# OMNIBUS_Stepper_board_v2.net
KiCad netlist of a schematic drawn in EAGLE
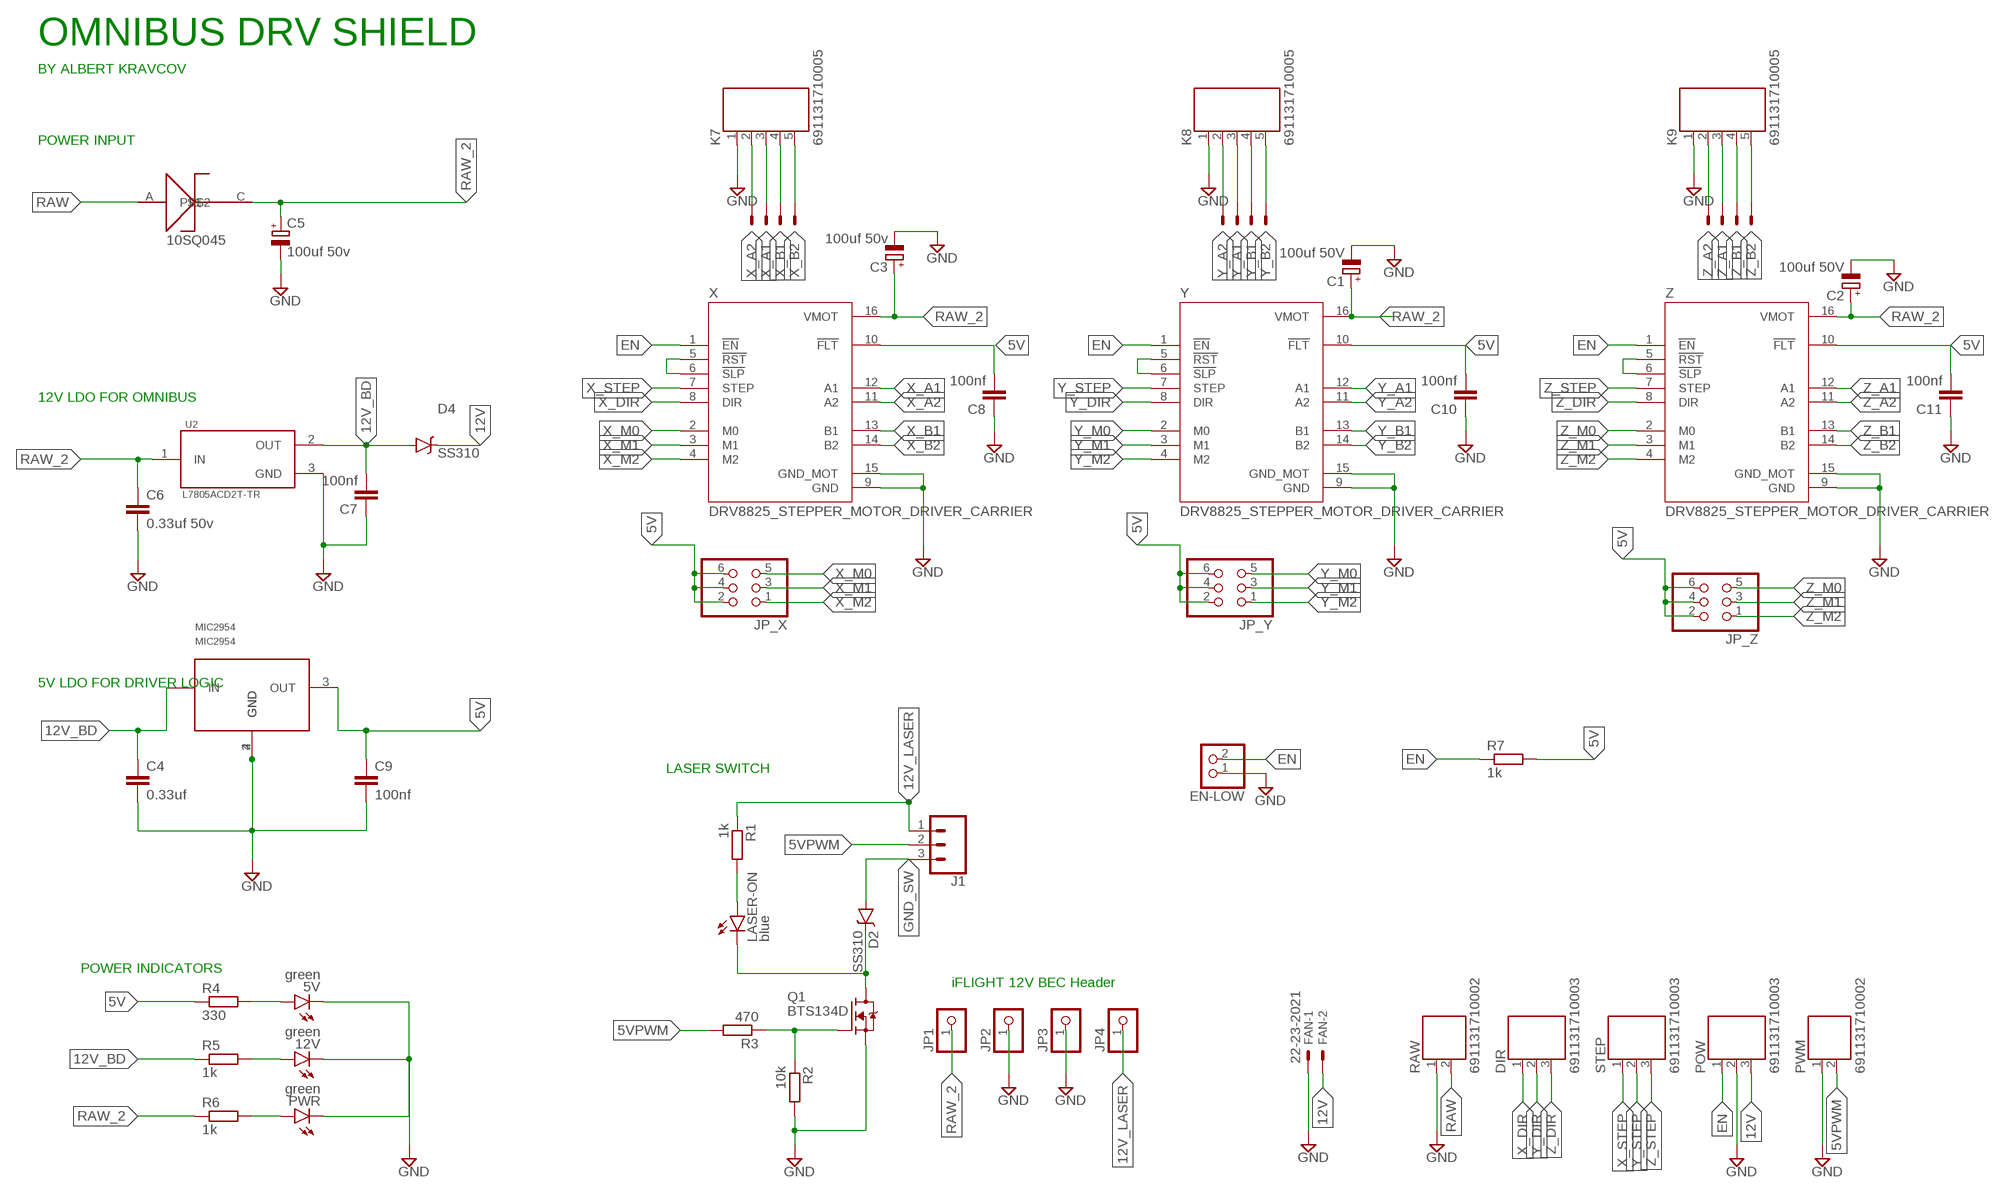
[diagram p0: schematic, sheet 1]

(export (version "E")
  (design (tool "Eeschema 10.0.6"))
  (components
    (comp (ref "5V")
      (value "green")
      (footprint "eagle-import:CHIPLED_0805")
      (libsource (lib "eagle-import") (part "LEDCHIPLED_0805"))
    )
    (comp (ref "12V")
      (value "green")
      (footprint "eagle-import:CHIPLED_0805")
      (libsource (lib "eagle-import") (part "LEDCHIPLED_0805"))
    )
    (comp (ref "C1")
      (value "100uf 50V")
      (footprint "eagle-import:E5-6")
      (libsource (lib "eagle-import") (part "CPOL-EUE5-6"))
    )
    (comp (ref "C2")
      (value "100uf 50V")
      (footprint "eagle-import:E5-6")
      (libsource (lib "eagle-import") (part "CPOL-EUE5-6"))
    )
    (comp (ref "C3")
      (value "100uf 50v")
      (footprint "eagle-import:E5-6")
      (libsource (lib "eagle-import") (part "CPOL-EUE5-6"))
    )
    (comp (ref "C4")
      (value "0.33uf")
      (footprint "eagle-import:C1206")
      (libsource (lib "eagle-import") (part "C-EUC1206"))
    )
    (comp (ref "C5")
      (value "100uf 50v")
      (footprint "eagle-import:E5-8,5")
      (libsource (lib "eagle-import") (part "rcl_334_CPOL-EUE5-8.5"))
    )
    (comp (ref "C6")
      (value "0.33uf 50v")
      (footprint "eagle-import:C1206")
      (libsource (lib "eagle-import") (part "C-EUC1206"))
    )
    (comp (ref "C7")
      (value "100nf")
      (footprint "eagle-import:C0805")
      (libsource (lib "eagle-import") (part "C-EUC0805"))
    )
    (comp (ref "C8")
      (value "100nf")
      (footprint "eagle-import:C0805")
      (libsource (lib "eagle-import") (part "C-EUC0805"))
    )
    (comp (ref "C9")
      (value "100nf")
      (footprint "eagle-import:C1206")
      (libsource (lib "eagle-import") (part "C-EUC1206"))
    )
    (comp (ref "C10")
      (value "100nf")
      (footprint "eagle-import:C0805")
      (libsource (lib "eagle-import") (part "C-EUC0805"))
    )
    (comp (ref "C11")
      (value "100nf")
      (footprint "eagle-import:C0805")
      (libsource (lib "eagle-import") (part "C-EUC0805"))
    )
    (comp (ref "D1")
      (value "10SQ045")
      (footprint "eagle-import:DIOAD885W125L910D885")
      (libsource (lib "eagle-import") (part "10SQ050"))
    )
    (comp (ref "D2")
      (value "SS310")
      (footprint "eagle-import:DO-214AC")
      (fields (field (name "MF") "Honeywell Sensing") (field (name "MP") "SS54"))
      (libsource (lib "eagle-import") (part "SS54"))
    )
    (comp (ref "D4")
      (value "SS310")
      (footprint "eagle-import:DO-214AC")
      (fields (field (name "MF") "Honeywell Sensing") (field (name "MP") "SS54"))
      (libsource (lib "eagle-import") (part "SS54"))
    )
    (comp (ref "DIR")
      (value "691131710003")
      (footprint "eagle-import:691131710003")
      (libsource (lib "eagle-import") (part "691131710003"))
    )
    (comp (ref "EN-LOW")
      (value "PINHD-1X2")
      (footprint "eagle-import:1X02")
      (libsource (lib "eagle-import") (part "PINHD-1X2"))
    )
    (comp (ref "FAN")
      (value "22-23-2021")
      (footprint "eagle-import:22-23-2021")
      (fields (field (name "MF") "MOLEX"))
      (libsource (lib "eagle-import") (part "22-23-2021"))
    )
    (comp (ref "J1")
      (value "CONN_03")
      (footprint "eagle-import:1X03")
      (libsource (lib "eagle-import") (part "CONN_03"))
    )
    (comp (ref "JP1")
      (value "PINHD-1X1")
      (footprint "eagle-import:1X01")
      (libsource (lib "eagle-import") (part "PINHD-1X1"))
    )
    (comp (ref "JP2")
      (value "PINHD-1X1")
      (footprint "eagle-import:1X01")
      (libsource (lib "eagle-import") (part "PINHD-1X1"))
    )
    (comp (ref "JP3")
      (value "PINHD-1X1")
      (footprint "eagle-import:1X01")
      (libsource (lib "eagle-import") (part "PINHD-1X1"))
    )
    (comp (ref "JP4")
      (value "PINHD-1X1")
      (footprint "eagle-import:1X01")
      (libsource (lib "eagle-import") (part "PINHD-1X1"))
    )
    (comp (ref "JP_X")
      (value "PINHD-2X3")
      (footprint "eagle-import:2X03")
      (libsource (lib "eagle-import") (part "PINHD-2X3"))
    )
    (comp (ref "JP_Y")
      (value "PINHD-2X3")
      (footprint "eagle-import:2X03")
      (libsource (lib "eagle-import") (part "PINHD-2X3"))
    )
    (comp (ref "JP_Z")
      (value "PINHD-2X3")
      (footprint "eagle-import:2X03")
      (libsource (lib "eagle-import") (part "PINHD-2X3"))
    )
    (comp (ref "K7")
      (value "691131710005")
      (footprint "eagle-import:691131710005")
      (libsource (lib "eagle-import") (part "691131710005"))
    )
    (comp (ref "K8")
      (value "691131710005")
      (footprint "eagle-import:691131710005")
      (libsource (lib "eagle-import") (part "691131710005"))
    )
    (comp (ref "K9")
      (value "691131710005")
      (footprint "eagle-import:691131710005")
      (libsource (lib "eagle-import") (part "691131710005"))
    )
    (comp (ref "LASER-ON")
      (value "blue")
      (footprint "eagle-import:CHIPLED_0805")
      (libsource (lib "eagle-import") (part "LEDCHIPLED_0805"))
    )
    (comp (ref "MIC2954")
      (value "MIC2954")
      (footprint "eagle-import:SOT223")
      (fields (field (name "MF") "Micrel"))
      (libsource (lib "eagle-import") (part "MIC2954"))
    )
    (comp (ref "POW")
      (value "691131710003")
      (footprint "eagle-import:691131710003")
      (libsource (lib "eagle-import") (part "691131710003"))
    )
    (comp (ref "PWM")
      (value "691131710002")
      (footprint "eagle-import:691131710002")
      (libsource (lib "eagle-import") (part "691131710002"))
    )
    (comp (ref "PWR")
      (value "green")
      (footprint "eagle-import:CHIPLED_0805")
      (libsource (lib "eagle-import") (part "LEDCHIPLED_0805"))
    )
    (comp (ref "Q1")
      (value "BTS134D")
      (footprint "eagle-import:TO-252")
      (fields (field (name "MF") "ON Semiconductor") (field (name "MP") "FQD7N10LTM"))
      (libsource (lib "eagle-import") (part "FQD7N10LTM"))
    )
    (comp (ref "R1")
      (value "1k")
      (footprint "eagle-import:R0805")
      (libsource (lib "eagle-import") (part "R-EU_R0805"))
    )
    (comp (ref "R2")
      (value "10k")
      (footprint "eagle-import:R0805")
      (libsource (lib "eagle-import") (part "R-EU_R0805"))
    )
    (comp (ref "R3")
      (value "470")
      (footprint "eagle-import:R0805")
      (libsource (lib "eagle-import") (part "R-EU_R0805"))
    )
    (comp (ref "R4")
      (value "330")
      (footprint "eagle-import:R0805")
      (libsource (lib "eagle-import") (part "R-EU_R0805"))
    )
    (comp (ref "R5")
      (value "1k")
      (footprint "eagle-import:R0805")
      (libsource (lib "eagle-import") (part "R-EU_R0805"))
    )
    (comp (ref "R6")
      (value "1k")
      (footprint "eagle-import:R1206")
      (libsource (lib "eagle-import") (part "R-EU_R1206"))
    )
    (comp (ref "R7")
      (value "1k")
      (footprint "eagle-import:R0805")
      (libsource (lib "eagle-import") (part "R-EU_R0805"))
    )
    (comp (ref "RAW")
      (value "691131710002")
      (footprint "eagle-import:691131710002")
      (libsource (lib "eagle-import") (part "691131710002"))
    )
    (comp (ref "STEP")
      (value "691131710003")
      (footprint "eagle-import:691131710003")
      (libsource (lib "eagle-import") (part "691131710003"))
    )
    (comp (ref "U2")
      (value "L7805ACD2T-TR")
      (footprint "eagle-import:TO254P1515X470-3N")
      (fields (field (name "MF") "STMicroelectronics"))
      (libsource (lib "eagle-import") (part "L7805ACD2T-TR"))
    )
    (comp (ref "X")
      (value "DRV8825_STEPPER_MOTOR_DRIVER_CARRIER")
      (footprint "eagle-import:IC_DRV8825_STEPPER_MOTOR_DRIVER_CARRIER")
      (fields (field (name "MF") "Pololu") (field (name "MP") "DRV8825 STEPPER MOTOR DRIVER CARRIER"))
      (libsource (lib "eagle-import") (part "DRV8825_STEPPER_MOTOR_DRIVER_CARRIER"))
    )
    (comp (ref "X_MOTOR")
      (value "22-23-2041")
      (footprint "eagle-import:22-23-2041")
      (fields (field (name "MF") "MOLEX"))
      (libsource (lib "eagle-import") (part "22-23-2041"))
    )
    (comp (ref "Y")
      (value "DRV8825_STEPPER_MOTOR_DRIVER_CARRIER")
      (footprint "eagle-import:IC_DRV8825_STEPPER_MOTOR_DRIVER_CARRIER")
      (fields (field (name "MF") "Pololu") (field (name "MP") "DRV8825 STEPPER MOTOR DRIVER CARRIER"))
      (libsource (lib "eagle-import") (part "DRV8825_STEPPER_MOTOR_DRIVER_CARRIER"))
    )
    (comp (ref "Y_MOTOR")
      (value "22-23-2041")
      (footprint "eagle-import:22-23-2041")
      (fields (field (name "MF") "MOLEX"))
      (libsource (lib "eagle-import") (part "22-23-2041"))
    )
    (comp (ref "Z")
      (value "DRV8825_STEPPER_MOTOR_DRIVER_CARRIER")
      (footprint "eagle-import:IC_DRV8825_STEPPER_MOTOR_DRIVER_CARRIER")
      (fields (field (name "MF") "Pololu") (field (name "MP") "DRV8825 STEPPER MOTOR DRIVER CARRIER"))
      (libsource (lib "eagle-import") (part "DRV8825_STEPPER_MOTOR_DRIVER_CARRIER"))
    )
    (comp (ref "Z_MOTOR")
      (value "22-23-2041")
      (footprint "eagle-import:22-23-2041")
      (fields (field (name "MF") "MOLEX"))
      (libsource (lib "eagle-import") (part "22-23-2041"))
    )
  )
  (nets
    (net (code "1") (name "5V") (class "Default")
      (node (ref "C10") (pin "2") (pinfunction "2_2") (pintype "passive"))
      (node (ref "C11") (pin "2") (pinfunction "2_2") (pintype "passive"))
      (node (ref "C8") (pin "2") (pinfunction "2_2") (pintype "passive"))
      (node (ref "C9") (pin "1") (pinfunction "1_1") (pintype "passive"))
      (node (ref "JP_X") (pin "2") (pinfunction "2_2") (pintype "passive"))
      (node (ref "JP_X") (pin "4") (pinfunction "4_4") (pintype "passive"))
      (node (ref "JP_X") (pin "6") (pinfunction "6_6") (pintype "passive"))
      (node (ref "JP_Y") (pin "2") (pinfunction "2_2") (pintype "passive"))
      (node (ref "JP_Y") (pin "4") (pinfunction "4_4") (pintype "passive"))
      (node (ref "JP_Y") (pin "6") (pinfunction "6_6") (pintype "passive"))
      (node (ref "JP_Z") (pin "2") (pinfunction "2_2") (pintype "passive"))
      (node (ref "JP_Z") (pin "4") (pinfunction "4_4") (pintype "passive"))
      (node (ref "JP_Z") (pin "6") (pinfunction "6_6") (pintype "passive"))
      (node (ref "MIC2954") (pin "3") (pinfunction "OUT_3") (pintype "bidirectional"))
      (node (ref "R4") (pin "1") (pinfunction "1_1") (pintype "passive"))
      (node (ref "R7") (pin "2") (pinfunction "2_2") (pintype "passive"))
      (node (ref "X") (pin "10") (pinfunction "~{FLT}_10") (pintype "output"))
      (node (ref "Y") (pin "10") (pinfunction "~{FLT}_10") (pintype "output"))
      (node (ref "Z") (pin "10") (pinfunction "~{FLT}_10") (pintype "output"))
    )
    (net (code "2") (name "5VPWM") (class "Default")
      (node (ref "J1") (pin "2") (pinfunction "2_2") (pintype "passive"))
      (node (ref "PWM") (pin "2") (pinfunction "2_2") (pintype "passive"))
      (node (ref "R3") (pin "2") (pinfunction "2_2") (pintype "passive"))
    )
    (net (code "3") (name "12V") (class "Default")
      (node (ref "D4") (pin "C") (pinfunction "C_C") (pintype "passive"))
      (node (ref "FAN") (pin "2") (pinfunction "S_2") (pintype "passive"))
      (node (ref "POW") (pin "3") (pinfunction "3_3") (pintype "passive"))
    )
    (net (code "4") (name "12V_BD") (class "Default")
      (node (ref "C4") (pin "1") (pinfunction "1_1") (pintype "passive"))
      (node (ref "C7") (pin "2") (pinfunction "2_2") (pintype "passive"))
      (node (ref "D4") (pin "A") (pinfunction "A_A") (pintype "passive"))
      (node (ref "MIC2954") (pin "1") (pinfunction "IN_1") (pintype "bidirectional"))
      (node (ref "R5") (pin "1") (pinfunction "1_1") (pintype "passive"))
      (node (ref "U2") (pin "2") (pinfunction "OUT_2") (pintype "output"))
    )
    (net (code "5") (name "12V_LASER") (class "Default")
      (node (ref "J1") (pin "1") (pinfunction "1_1") (pintype "passive"))
      (node (ref "JP4") (pin "1") (pinfunction "1_1") (pintype "passive"))
      (node (ref "R1") (pin "1") (pinfunction "1_1") (pintype "passive"))
    )
    (net (code "6") (name "EN") (class "Default")
      (node (ref "EN-LOW") (pin "2") (pinfunction "2_2") (pintype "passive"))
      (node (ref "POW") (pin "1") (pinfunction "1_1") (pintype "passive"))
      (node (ref "R7") (pin "1") (pinfunction "1_1") (pintype "passive"))
      (node (ref "X") (pin "1") (pinfunction "~{EN}_1") (pintype "input"))
      (node (ref "Y") (pin "1") (pinfunction "~{EN}_1") (pintype "input"))
      (node (ref "Z") (pin "1") (pinfunction "~{EN}_1") (pintype "input"))
    )
    (net (code "7") (name "GND") (class "Default")
      (node (ref "12V") (pin "C") (pinfunction "C_C") (pintype "passive"))
      (node (ref "5V") (pin "C") (pinfunction "C_C") (pintype "passive"))
      (node (ref "C1") (pin "-") (pinfunction "-_-") (pintype "passive"))
      (node (ref "C10") (pin "1") (pinfunction "1_1") (pintype "passive"))
      (node (ref "C11") (pin "1") (pinfunction "1_1") (pintype "passive"))
      (node (ref "C2") (pin "-") (pinfunction "-_-") (pintype "passive"))
      (node (ref "C3") (pin "-") (pinfunction "-_-") (pintype "passive"))
      (node (ref "C4") (pin "2") (pinfunction "2_2") (pintype "passive"))
      (node (ref "C5") (pin "-") (pinfunction "-_-") (pintype "passive"))
      (node (ref "C6") (pin "2") (pinfunction "2_2") (pintype "passive"))
      (node (ref "C7") (pin "1") (pinfunction "1_1") (pintype "passive"))
      (node (ref "C8") (pin "1") (pinfunction "1_1") (pintype "passive"))
      (node (ref "C9") (pin "2") (pinfunction "2_2") (pintype "passive"))
      (node (ref "EN-LOW") (pin "1") (pinfunction "1_1") (pintype "passive"))
      (node (ref "FAN") (pin "1") (pinfunction "S_1") (pintype "passive"))
      (node (ref "JP2") (pin "1") (pinfunction "1_1") (pintype "passive"))
      (node (ref "JP3") (pin "1") (pinfunction "1_1") (pintype "passive"))
      (node (ref "K7") (pin "1") (pinfunction "1_1") (pintype "passive"))
      (node (ref "K8") (pin "1") (pinfunction "1_1") (pintype "passive"))
      (node (ref "K9") (pin "1") (pinfunction "1_1") (pintype "passive"))
      (node (ref "MIC2954") (pin "2") (pinfunction "GND_2") (pintype "bidirectional"))
      (node (ref "MIC2954") (pin "4") (pinfunction "GND_4") (pintype "bidirectional"))
      (node (ref "POW") (pin "2") (pinfunction "2_2") (pintype "passive"))
      (node (ref "PWM") (pin "1") (pinfunction "1_1") (pintype "passive"))
      (node (ref "PWR") (pin "C") (pinfunction "C_C") (pintype "passive"))
      (node (ref "Q1") (pin "3") (pinfunction "S_3") (pintype "passive"))
      (node (ref "R2") (pin "2") (pinfunction "2_2") (pintype "passive"))
      (node (ref "RAW") (pin "1") (pinfunction "1_1") (pintype "passive"))
      (node (ref "U2") (pin "3") (pinfunction "GND_3") (pintype "power_in"))
      (node (ref "X") (pin "15") (pinfunction "GND_MOT_15") (pintype "power_in"))
      (node (ref "X") (pin "9") (pinfunction "GND_9") (pintype "power_in"))
      (node (ref "Y") (pin "15") (pinfunction "GND_MOT_15") (pintype "power_in"))
      (node (ref "Y") (pin "9") (pinfunction "GND_9") (pintype "power_in"))
      (node (ref "Z") (pin "15") (pinfunction "GND_MOT_15") (pintype "power_in"))
      (node (ref "Z") (pin "9") (pinfunction "GND_9") (pintype "power_in"))
    )
    (net (code "8") (name "GND_SW") (class "Default")
      (node (ref "D2") (pin "A") (pinfunction "A_A") (pintype "passive"))
      (node (ref "J1") (pin "3") (pinfunction "3_3") (pintype "passive"))
    )
    (net (code "9") (name "Net-(5V-PadA)") (class "Default")
      (node (ref "5V") (pin "A") (pinfunction "A_A") (pintype "passive"))
      (node (ref "R4") (pin "2") (pinfunction "2_2") (pintype "passive"))
    )
    (net (code "10") (name "Net-(12V-PadA)") (class "Default")
      (node (ref "12V") (pin "A") (pinfunction "A_A") (pintype "passive"))
      (node (ref "R5") (pin "2") (pinfunction "2_2") (pintype "passive"))
    )
    (net (code "11") (name "Net-(LASER-ON-PadA)") (class "Default")
      (node (ref "LASER-ON") (pin "A") (pinfunction "A_A") (pintype "passive"))
      (node (ref "R1") (pin "2") (pinfunction "2_2") (pintype "passive"))
    )
    (net (code "12") (name "Net-(PWR-PadA)") (class "Default")
      (node (ref "PWR") (pin "A") (pinfunction "A_A") (pintype "passive"))
      (node (ref "R6") (pin "2") (pinfunction "2_2") (pintype "passive"))
    )
    (net (code "13") (name "Net-(Q1-D)") (class "Default")
      (node (ref "D2") (pin "C") (pinfunction "C_C") (pintype "passive"))
      (node (ref "LASER-ON") (pin "C") (pinfunction "C_C") (pintype "passive"))
      (node (ref "Q1") (pin "T") (pinfunction "D_T") (pintype "passive"))
    )
    (net (code "14") (name "Net-(Q1-G)") (class "Default")
      (node (ref "Q1") (pin "1") (pinfunction "G_1") (pintype "passive"))
      (node (ref "R2") (pin "1") (pinfunction "1_1") (pintype "passive"))
      (node (ref "R3") (pin "1") (pinfunction "1_1") (pintype "passive"))
    )
    (net (code "15") (name "Net-(X-~{RST})") (class "Default")
      (node (ref "X") (pin "5") (pinfunction "~{RST}_5") (pintype "input"))
      (node (ref "X") (pin "6") (pinfunction "~{SLP}_6") (pintype "input"))
    )
    (net (code "16") (name "Net-(Y-~{RST})") (class "Default")
      (node (ref "Y") (pin "5") (pinfunction "~{RST}_5") (pintype "input"))
      (node (ref "Y") (pin "6") (pinfunction "~{SLP}_6") (pintype "input"))
    )
    (net (code "17") (name "Net-(Z-~{RST})") (class "Default")
      (node (ref "Z") (pin "5") (pinfunction "~{RST}_5") (pintype "input"))
      (node (ref "Z") (pin "6") (pinfunction "~{SLP}_6") (pintype "input"))
    )
    (net (code "18") (name "RAW") (class "Default")
      (node (ref "D1") (pin "A") (pinfunction "P$1_A") (pintype "bidirectional"))
      (node (ref "RAW") (pin "2") (pinfunction "2_2") (pintype "passive"))
    )
    (net (code "19") (name "RAW_2") (class "Default")
      (node (ref "C1") (pin "+") (pinfunction "+_+") (pintype "passive"))
      (node (ref "C2") (pin "+") (pinfunction "+_+") (pintype "passive"))
      (node (ref "C3") (pin "+") (pinfunction "+_+") (pintype "passive"))
      (node (ref "C5") (pin "+") (pinfunction "+_+") (pintype "passive"))
      (node (ref "C6") (pin "1") (pinfunction "1_1") (pintype "passive"))
      (node (ref "D1") (pin "C") (pinfunction "P$2_C") (pintype "bidirectional"))
      (node (ref "JP1") (pin "1") (pinfunction "1_1") (pintype "passive"))
      (node (ref "R6") (pin "1") (pinfunction "1_1") (pintype "passive"))
      (node (ref "U2") (pin "1") (pinfunction "IN_1") (pintype "input"))
      (node (ref "X") (pin "16") (pinfunction "VMOT_16") (pintype "power_in"))
      (node (ref "Y") (pin "16") (pinfunction "VMOT_16") (pintype "power_in"))
      (node (ref "Z") (pin "16") (pinfunction "VMOT_16") (pintype "power_in"))
    )
    (net (code "20") (name "X_A1") (class "Default")
      (node (ref "K7") (pin "3") (pinfunction "3_3") (pintype "passive"))
      (node (ref "X") (pin "12") (pinfunction "A1_12") (pintype "output"))
      (node (ref "X_MOTOR") (pin "3") (pinfunction "S_3") (pintype "passive"))
    )
    (net (code "21") (name "X_A2") (class "Default")
      (node (ref "K7") (pin "2") (pinfunction "2_2") (pintype "passive"))
      (node (ref "X") (pin "11") (pinfunction "A2_11") (pintype "output"))
      (node (ref "X_MOTOR") (pin "4") (pinfunction "S_4") (pintype "passive"))
    )
    (net (code "22") (name "X_B1") (class "Default")
      (node (ref "K7") (pin "4") (pinfunction "4_4") (pintype "passive"))
      (node (ref "X") (pin "13") (pinfunction "B1_13") (pintype "output"))
      (node (ref "X_MOTOR") (pin "2") (pinfunction "S_2") (pintype "passive"))
    )
    (net (code "23") (name "X_B2") (class "Default")
      (node (ref "K7") (pin "5") (pinfunction "5_5") (pintype "passive"))
      (node (ref "X") (pin "14") (pinfunction "B2_14") (pintype "output"))
      (node (ref "X_MOTOR") (pin "1") (pinfunction "S_1") (pintype "passive"))
    )
    (net (code "24") (name "X_DIR") (class "Default")
      (node (ref "DIR") (pin "1") (pinfunction "1_1") (pintype "passive"))
      (node (ref "X") (pin "8") (pinfunction "DIR_8") (pintype "input"))
    )
    (net (code "25") (name "X_M0") (class "Default")
      (node (ref "JP_X") (pin "5") (pinfunction "5_5") (pintype "passive"))
      (node (ref "X") (pin "2") (pinfunction "M0_2") (pintype "input"))
    )
    (net (code "26") (name "X_M1") (class "Default")
      (node (ref "JP_X") (pin "3") (pinfunction "3_3") (pintype "passive"))
      (node (ref "X") (pin "3") (pinfunction "M1_3") (pintype "input"))
    )
    (net (code "27") (name "X_M2") (class "Default")
      (node (ref "JP_X") (pin "1") (pinfunction "1_1") (pintype "passive"))
      (node (ref "X") (pin "4") (pinfunction "M2_4") (pintype "input"))
    )
    (net (code "28") (name "X_STEP") (class "Default")
      (node (ref "STEP") (pin "1") (pinfunction "1_1") (pintype "passive"))
      (node (ref "X") (pin "7") (pinfunction "STEP_7") (pintype "input"))
    )
    (net (code "29") (name "Y_A1") (class "Default")
      (node (ref "K8") (pin "3") (pinfunction "3_3") (pintype "passive"))
      (node (ref "Y") (pin "12") (pinfunction "A1_12") (pintype "output"))
      (node (ref "Y_MOTOR") (pin "3") (pinfunction "S_3") (pintype "passive"))
    )
    (net (code "30") (name "Y_A2") (class "Default")
      (node (ref "K8") (pin "2") (pinfunction "2_2") (pintype "passive"))
      (node (ref "Y") (pin "11") (pinfunction "A2_11") (pintype "output"))
      (node (ref "Y_MOTOR") (pin "4") (pinfunction "S_4") (pintype "passive"))
    )
    (net (code "31") (name "Y_B1") (class "Default")
      (node (ref "K8") (pin "4") (pinfunction "4_4") (pintype "passive"))
      (node (ref "Y") (pin "13") (pinfunction "B1_13") (pintype "output"))
      (node (ref "Y_MOTOR") (pin "2") (pinfunction "S_2") (pintype "passive"))
    )
    (net (code "32") (name "Y_B2") (class "Default")
      (node (ref "K8") (pin "5") (pinfunction "5_5") (pintype "passive"))
      (node (ref "Y") (pin "14") (pinfunction "B2_14") (pintype "output"))
      (node (ref "Y_MOTOR") (pin "1") (pinfunction "S_1") (pintype "passive"))
    )
    (net (code "33") (name "Y_DIR") (class "Default")
      (node (ref "DIR") (pin "2") (pinfunction "2_2") (pintype "passive"))
      (node (ref "Y") (pin "8") (pinfunction "DIR_8") (pintype "input"))
    )
    (net (code "34") (name "Y_M0") (class "Default")
      (node (ref "JP_Y") (pin "5") (pinfunction "5_5") (pintype "passive"))
      (node (ref "Y") (pin "2") (pinfunction "M0_2") (pintype "input"))
    )
    (net (code "35") (name "Y_M1") (class "Default")
      (node (ref "JP_Y") (pin "3") (pinfunction "3_3") (pintype "passive"))
      (node (ref "Y") (pin "3") (pinfunction "M1_3") (pintype "input"))
    )
    (net (code "36") (name "Y_M2") (class "Default")
      (node (ref "JP_Y") (pin "1") (pinfunction "1_1") (pintype "passive"))
      (node (ref "Y") (pin "4") (pinfunction "M2_4") (pintype "input"))
    )
    (net (code "37") (name "Y_STEP") (class "Default")
      (node (ref "STEP") (pin "2") (pinfunction "2_2") (pintype "passive"))
      (node (ref "Y") (pin "7") (pinfunction "STEP_7") (pintype "input"))
    )
    (net (code "38") (name "Z_A1") (class "Default")
      (node (ref "K9") (pin "3") (pinfunction "3_3") (pintype "passive"))
      (node (ref "Z") (pin "12") (pinfunction "A1_12") (pintype "output"))
      (node (ref "Z_MOTOR") (pin "3") (pinfunction "S_3") (pintype "passive"))
    )
    (net (code "39") (name "Z_A2") (class "Default")
      (node (ref "K9") (pin "2") (pinfunction "2_2") (pintype "passive"))
      (node (ref "Z") (pin "11") (pinfunction "A2_11") (pintype "output"))
      (node (ref "Z_MOTOR") (pin "4") (pinfunction "S_4") (pintype "passive"))
    )
    (net (code "40") (name "Z_B1") (class "Default")
      (node (ref "K9") (pin "4") (pinfunction "4_4") (pintype "passive"))
      (node (ref "Z") (pin "13") (pinfunction "B1_13") (pintype "output"))
      (node (ref "Z_MOTOR") (pin "2") (pinfunction "S_2") (pintype "passive"))
    )
    (net (code "41") (name "Z_B2") (class "Default")
      (node (ref "K9") (pin "5") (pinfunction "5_5") (pintype "passive"))
      (node (ref "Z") (pin "14") (pinfunction "B2_14") (pintype "output"))
      (node (ref "Z_MOTOR") (pin "1") (pinfunction "S_1") (pintype "passive"))
    )
    (net (code "42") (name "Z_DIR") (class "Default")
      (node (ref "DIR") (pin "3") (pinfunction "3_3") (pintype "passive"))
      (node (ref "Z") (pin "8") (pinfunction "DIR_8") (pintype "input"))
    )
    (net (code "43") (name "Z_M0") (class "Default")
      (node (ref "JP_Z") (pin "5") (pinfunction "5_5") (pintype "passive"))
      (node (ref "Z") (pin "2") (pinfunction "M0_2") (pintype "input"))
    )
    (net (code "44") (name "Z_M1") (class "Default")
      (node (ref "JP_Z") (pin "3") (pinfunction "3_3") (pintype "passive"))
      (node (ref "Z") (pin "3") (pinfunction "M1_3") (pintype "input"))
    )
    (net (code "45") (name "Z_M2") (class "Default")
      (node (ref "JP_Z") (pin "1") (pinfunction "1_1") (pintype "passive"))
      (node (ref "Z") (pin "4") (pinfunction "M2_4") (pintype "input"))
    )
    (net (code "46") (name "Z_STEP") (class "Default")
      (node (ref "STEP") (pin "3") (pinfunction "3_3") (pintype "passive"))
      (node (ref "Z") (pin "7") (pinfunction "STEP_7") (pintype "input"))
    )
  )
)
